# 03b_StepperMotorDriver.net
KiCad netlist of a schematic drawn in Altium Designer
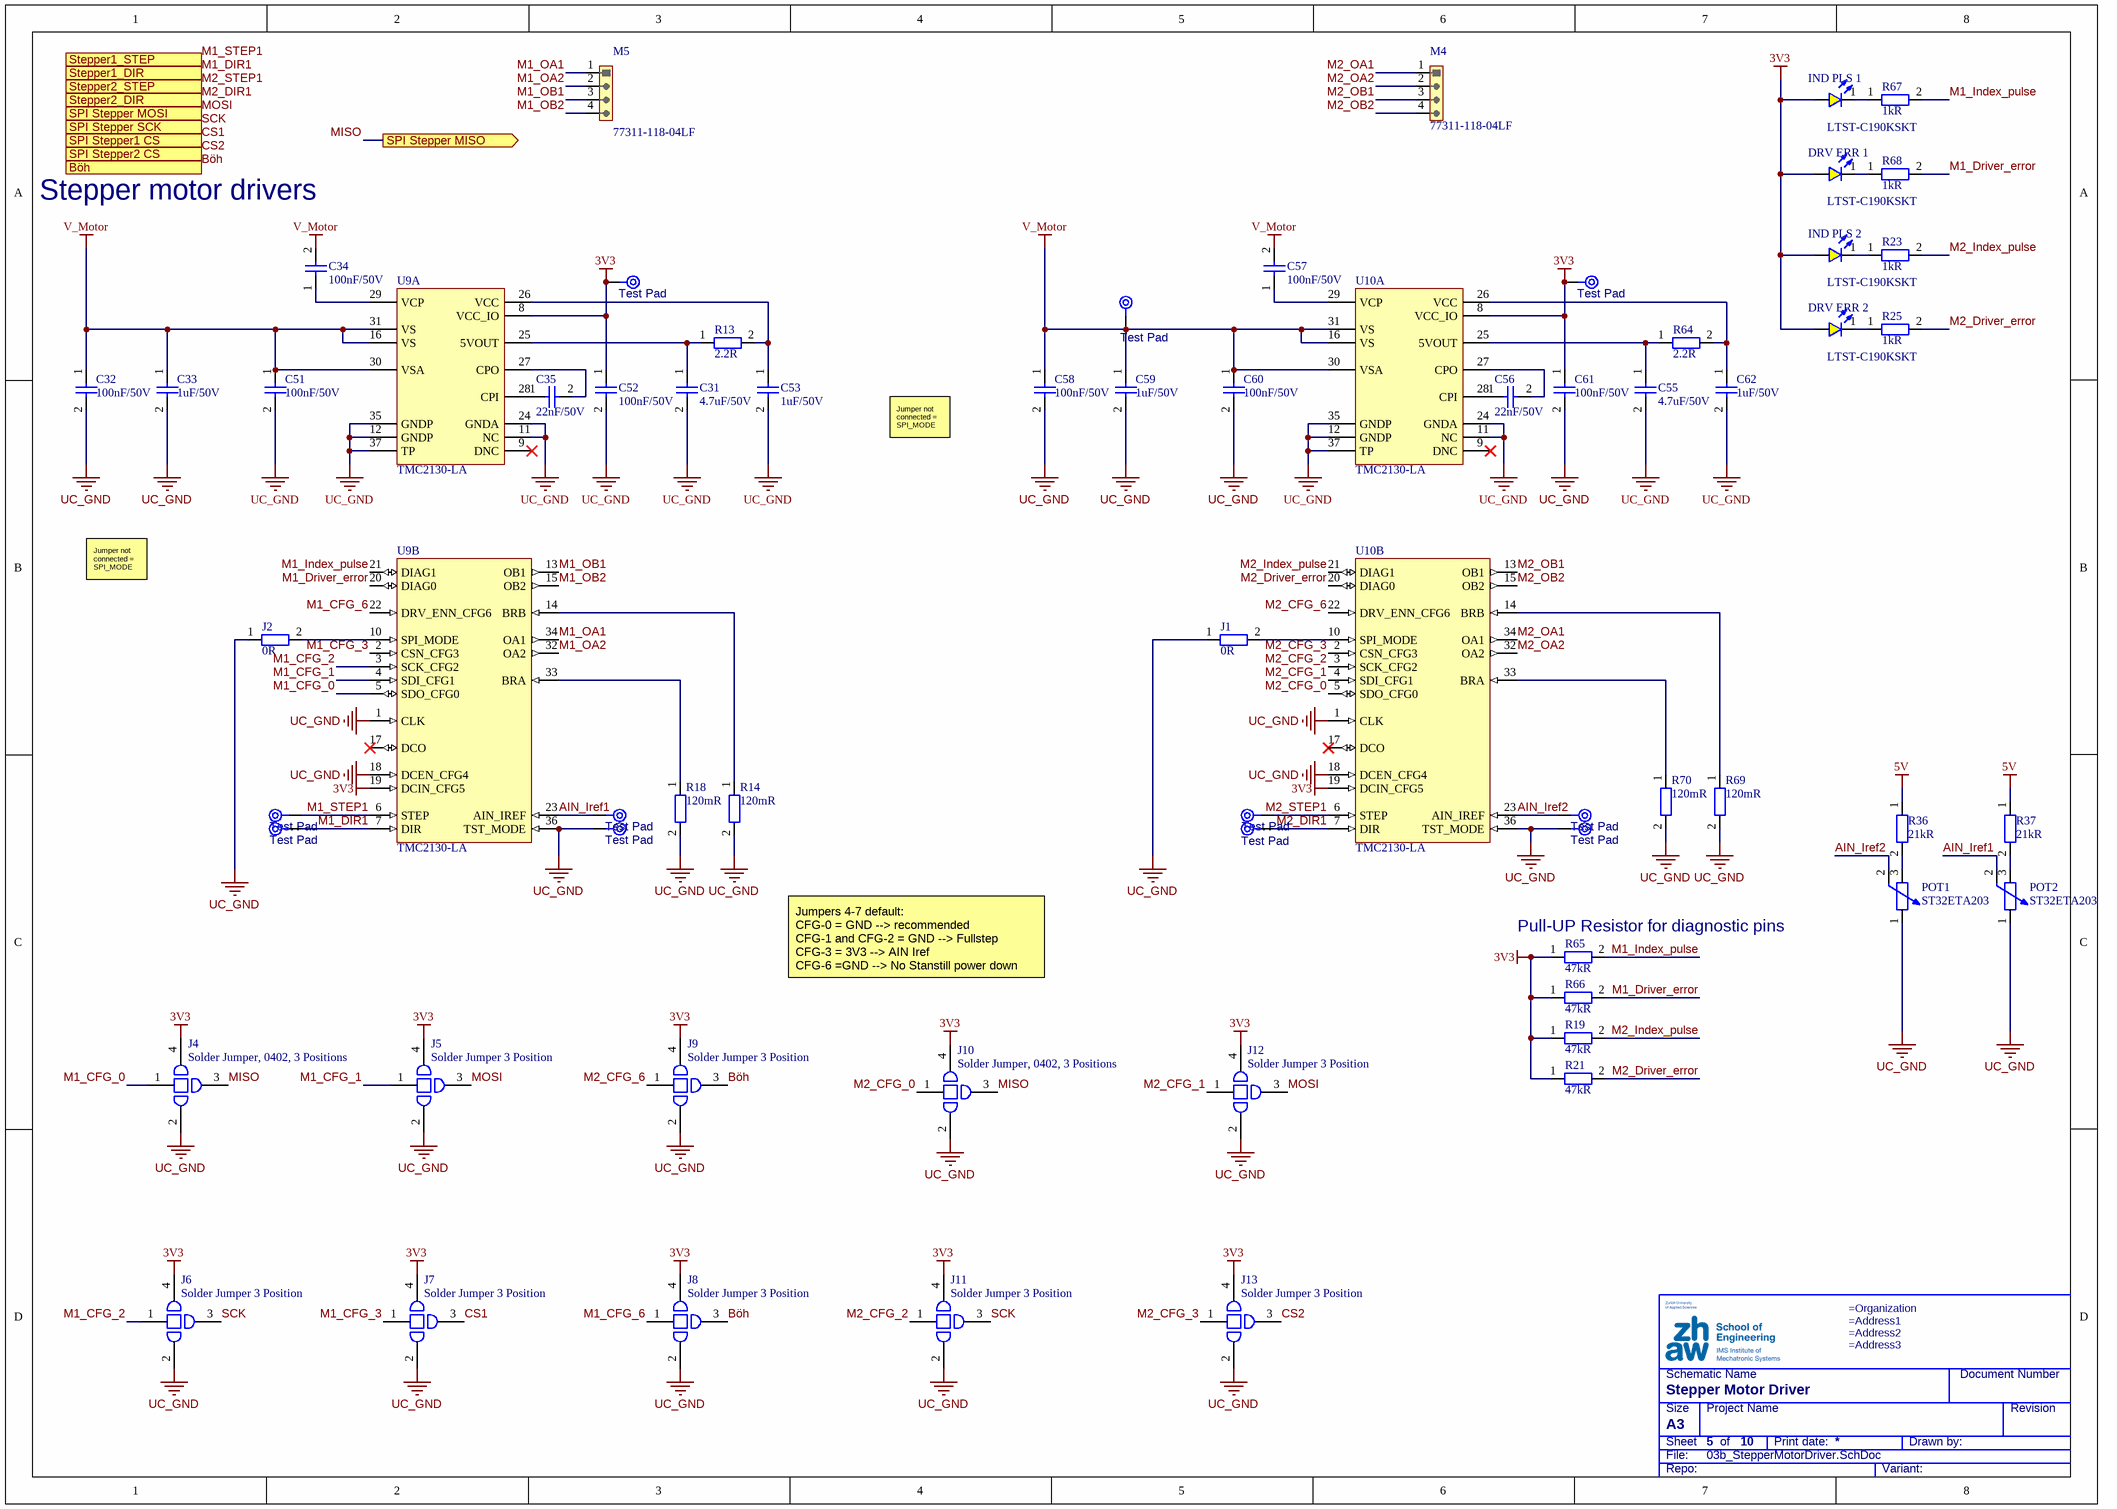
[diagram p0: 03b_StepperMotorDriver.SchDoc]

(export (version "E")
  (design (tool "Eeschema 10.0.6"))
  (components
    (comp (ref "6_M1_STEP")
      (value "Test Pad")
      (footprint "TP10R")
      (description "Test Pad 1.0 mm, SMD, d1.0")
      (libsource (lib "Altium Concord Pro on Altium 365") (part "Test Pad"))
    )
    (comp (ref "6_STEP_2")
      (value "Test Pad")
      (footprint "TP10R")
      (description "Test Pad 1.0 mm, SMD, d1.0")
      (libsource (lib "Altium Concord Pro on Altium 365") (part "Test Pad"))
    )
    (comp (ref "7_DIR_2")
      (value "Test Pad")
      (footprint "TP10R")
      (description "Test Pad 1.0 mm, SMD, d1.0")
      (libsource (lib "Altium Concord Pro on Altium 365") (part "Test Pad"))
    )
    (comp (ref "7_M1_DIR")
      (value "Test Pad")
      (footprint "TP10R")
      (description "Test Pad 1.0 mm, SMD, d1.0")
      (libsource (lib "Altium Concord Pro on Altium 365") (part "Test Pad"))
    )
    (comp (ref "8_VCC_IO")
      (value "Test Pad")
      (footprint "TP10R")
      (description "Test Pad 1.0 mm, SMD, d1.0")
      (libsource (lib "Altium Concord Pro on Altium 365") (part "Test Pad"))
    )
    (comp (ref "8_VCC_IO_2")
      (value "Test Pad")
      (footprint "TP10R")
      (description "Test Pad 1.0 mm, SMD, d1.0")
      (libsource (lib "Altium Concord Pro on Altium 365") (part "Test Pad"))
    )
    (comp (ref "16_31_VS_2")
      (value "Test Pad")
      (footprint "TP10R")
      (description "Test Pad 1.0 mm, SMD, d1.0")
      (libsource (lib "Altium Concord Pro on Altium 365") (part "Test Pad"))
    )
    (comp (ref "23_AIN_IREF")
      (value "Test Pad")
      (footprint "TP10R")
      (description "Test Pad 1.0 mm, SMD, d1.0")
      (libsource (lib "Altium Concord Pro on Altium 365") (part "Test Pad"))
    )
    (comp (ref "23_AIN_IREF_2")
      (value "Test Pad")
      (footprint "TP10R")
      (description "Test Pad 1.0 mm, SMD, d1.0")
      (libsource (lib "Altium Concord Pro on Altium 365") (part "Test Pad"))
    )
    (comp (ref "36_TST_MODE")
      (value "Test Pad")
      (footprint "TP10R")
      (description "Test Pad 1.0 mm, SMD, d1.0")
      (libsource (lib "Altium Concord Pro on Altium 365") (part "Test Pad"))
    )
    (comp (ref "36_TST_MODE_2")
      (value "Test Pad")
      (footprint "TP10R")
      (description "Test Pad 1.0 mm, SMD, d1.0")
      (libsource (lib "Altium Concord Pro on Altium 365") (part "Test Pad"))
    )
    (comp (ref "C31")
      (value "4.7uF/50V")
      (footprint "CAPC2012X15L")
      (description "Cap MLCC, 4.7uF, 50V, X5R, 10%, 0805")
      (fields (field (name "TOLERANCE") "10%"))
      (libsource (lib "Altium Concord Pro on Altium 365") (part "CAP-NP-2"))
    )
    (comp (ref "C32")
      (value "100nF/50V")
      (footprint "CAPC1005X05L")
      (description "Cap MLCC, 100nF, 50V, X7R, 10%, 0402")
      (fields (field (name "TOLERANCE") "10%"))
      (libsource (lib "Altium Concord Pro on Altium 365") (part "CAP-NP-2"))
    )
    (comp (ref "C33")
      (value "1uF/50V")
      (footprint "CAPC1608X09L")
      (description "Cap MLCC, 1uF, 50V, X5R, 10%, 0603")
      (fields (field (name "TOLERANCE") "10%"))
      (libsource (lib "Altium Concord Pro on Altium 365") (part "CAP-NP-2"))
    )
    (comp (ref "C34")
      (value "100nF/50V")
      (footprint "CAPC1005X05L")
      (description "Cap MLCC, 100nF, 50V, X7R, 10%, 0402")
      (fields (field (name "TOLERANCE") "10%"))
      (libsource (lib "Altium Concord Pro on Altium 365") (part "CAP-NP-2"))
    )
    (comp (ref "C35")
      (value "22nF/50V")
      (footprint "CAPC1005X05L")
      (description "Cap MLCC, 22nF, 50V, X7R, 10%, 0402")
      (fields (field (name "TOLERANCE") "10%"))
      (libsource (lib "Altium Concord Pro on Altium 365") (part "CAP-NP-2"))
    )
    (comp (ref "C51")
      (value "100nF/50V")
      (footprint "CAPC1005X05L")
      (description "Cap MLCC, 100nF, 50V, X7R, 10%, 0402")
      (fields (field (name "TOLERANCE") "10%"))
      (libsource (lib "Altium Concord Pro on Altium 365") (part "CAP-NP-2"))
    )
    (comp (ref "C52")
      (value "100nF/50V")
      (footprint "CAPC1005X05L")
      (description "Cap MLCC, 100nF, 50V, X7R, 10%, 0402")
      (fields (field (name "TOLERANCE") "10%"))
      (libsource (lib "Altium Concord Pro on Altium 365") (part "CAP-NP-2"))
    )
    (comp (ref "C53")
      (value "1uF/50V")
      (footprint "CAPC1608X09L")
      (description "Cap MLCC, 1uF, 50V, X5R, 10%, 0603")
      (fields (field (name "TOLERANCE") "10%"))
      (libsource (lib "Altium Concord Pro on Altium 365") (part "CAP-NP-2"))
    )
    (comp (ref "C55")
      (value "4.7uF/50V")
      (footprint "CAPC2012X15L")
      (description "Cap MLCC, 4.7uF, 50V, X5R, 10%, 0805")
      (fields (field (name "TOLERANCE") "10%"))
      (libsource (lib "Altium Concord Pro on Altium 365") (part "CAP-NP-2"))
    )
    (comp (ref "C56")
      (value "22nF/50V")
      (footprint "CAPC1005X05L")
      (description "Cap MLCC, 22nF, 50V, X7R, 10%, 0402")
      (fields (field (name "TOLERANCE") "10%"))
      (libsource (lib "Altium Concord Pro on Altium 365") (part "CAP-NP-2"))
    )
    (comp (ref "C57")
      (value "100nF/50V")
      (footprint "CAPC1005X05L")
      (description "Cap MLCC, 100nF, 50V, X7R, 10%, 0402")
      (fields (field (name "TOLERANCE") "10%"))
      (libsource (lib "Altium Concord Pro on Altium 365") (part "CAP-NP-2"))
    )
    (comp (ref "C58")
      (value "100nF/50V")
      (footprint "CAPC1005X05L")
      (description "Cap MLCC, 100nF, 50V, X7R, 10%, 0402")
      (fields (field (name "TOLERANCE") "10%"))
      (libsource (lib "Altium Concord Pro on Altium 365") (part "CAP-NP-2"))
    )
    (comp (ref "C59")
      (value "1uF/50V")
      (footprint "CAPC1608X09L")
      (description "Cap MLCC, 1uF, 50V, X5R, 10%, 0603")
      (fields (field (name "TOLERANCE") "10%"))
      (libsource (lib "Altium Concord Pro on Altium 365") (part "CAP-NP-2"))
    )
    (comp (ref "C60")
      (value "100nF/50V")
      (footprint "CAPC1005X05L")
      (description "Cap MLCC, 100nF, 50V, X7R, 10%, 0402")
      (fields (field (name "TOLERANCE") "10%"))
      (libsource (lib "Altium Concord Pro on Altium 365") (part "CAP-NP-2"))
    )
    (comp (ref "C61")
      (value "100nF/50V")
      (footprint "CAPC1005X05L")
      (description "Cap MLCC, 100nF, 50V, X7R, 10%, 0402")
      (fields (field (name "TOLERANCE") "10%"))
      (libsource (lib "Altium Concord Pro on Altium 365") (part "CAP-NP-2"))
    )
    (comp (ref "C62")
      (value "1uF/50V")
      (footprint "CAPC1608X09L")
      (description "Cap MLCC, 1uF, 50V, X5R, 10%, 0603")
      (fields (field (name "TOLERANCE") "10%"))
      (libsource (lib "Altium Concord Pro on Altium 365") (part "CAP-NP-2"))
    )
    (comp (ref "DRV ERR 1")
      (value "LTST-C190KSKT")
      (footprint "LEDSC160X80X80-2Lye")
      (description "LED, Yellow, 20mA, 2.0V, 0603")
      (libsource (lib "Altium Concord Pro on Altium 365") (part "LED-YELLOW-AK-2"))
    )
    (comp (ref "DRV ERR 2")
      (value "LTST-C190KSKT")
      (footprint "LEDSC160X80X80-2Lye")
      (description "LED, Yellow, 20mA, 2.0V, 0603")
      (libsource (lib "Altium Concord Pro on Altium 365") (part "LED-YELLOW-AK-2"))
    )
    (comp (ref "IND PLS 1")
      (value "LTST-C190KSKT")
      (footprint "LEDSC160X80X80-2Lye")
      (description "LED, Yellow, 20mA, 2.0V, 0603")
      (libsource (lib "Altium Concord Pro on Altium 365") (part "LED-YELLOW-AK-2"))
    )
    (comp (ref "IND PLS 2")
      (value "LTST-C190KSKT")
      (footprint "LEDSC160X80X80-2Lye")
      (description "LED, Yellow, 20mA, 2.0V, 0603")
      (libsource (lib "Altium Concord Pro on Altium 365") (part "LED-YELLOW-AK-2"))
    )
    (comp (ref "J1")
      (value "0R")
      (footprint "RESC1005X04L")
      (description "Res, 0R, 1%, 0.063W, 0402")
      (fields (field (name "POWER") "63mW") (field (name "TOLERANCE") "1%"))
      (libsource (lib "") (part "RES-2_1"))
    )
    (comp (ref "J2")
      (value "0R")
      (footprint "RESC1005X04L")
      (description "Res, 0R, 1%, 0.063W, 0402")
      (fields (field (name "POWER") "63mW") (field (name "TOLERANCE") "1%"))
      (libsource (lib "") (part "RES-2_1"))
    )
    (comp (ref "J4")
      (value "Solder Jumper, 0402, 3 Positions")
      (footprint "Solder Jumper 3 Positions, Position 1")
      (description "Solder Jumper, 0402, 3 Positions, SMD")
      (libsource (lib "Altium Concord Pro on Altium 365") (part "Solder Jumper 3 Position"))
    )
    (comp (ref "J5")
      (value "Solder Jumper 3 Position")
      (footprint "Solder Jumper, 0402, 3 Positions, DNP")
      (description "Solder Jumper, 0402, 3 Positions, SMD")
      (libsource (lib "Altium Concord Pro on Altium 365") (part "Solder Jumper 3 Position"))
    )
    (comp (ref "J6")
      (value "Solder Jumper 3 Position")
      (footprint "Solder Jumper, 0402, 3 Positions, DNP")
      (description "Solder Jumper, 0402, 3 Positions, SMD")
      (libsource (lib "Altium Concord Pro on Altium 365") (part "Solder Jumper 3 Position"))
    )
    (comp (ref "J7")
      (value "Solder Jumper 3 Position")
      (footprint "Solder Jumper, 0402, 3 Positions, DNP")
      (description "Solder Jumper, 0402, 3 Positions, SMD")
      (libsource (lib "Altium Concord Pro on Altium 365") (part "Solder Jumper 3 Position"))
    )
    (comp (ref "J8")
      (value "Solder Jumper 3 Position")
      (footprint "Solder Jumper 3 Positions, Position 2")
      (description "Solder Jumper, 0402, 3 Positions, SMD")
      (libsource (lib "Altium Concord Pro on Altium 365") (part "Solder Jumper 3 Position"))
    )
    (comp (ref "J9")
      (value "Solder Jumper 3 Position")
      (footprint "Solder Jumper 3 Positions, Position 2")
      (description "Solder Jumper, 0402, 3 Positions, SMD")
      (libsource (lib "Altium Concord Pro on Altium 365") (part "Solder Jumper 3 Position"))
    )
    (comp (ref "J10")
      (value "Solder Jumper, 0402, 3 Positions")
      (footprint "Solder Jumper 3 Positions, Position 1")
      (description "Solder Jumper, 0402, 3 Positions, SMD")
      (libsource (lib "Altium Concord Pro on Altium 365") (part "Solder Jumper 3 Position"))
    )
    (comp (ref "J11")
      (value "Solder Jumper 3 Position")
      (footprint "Solder Jumper, 0402, 3 Positions, DNP")
      (description "Solder Jumper, 0402, 3 Positions, SMD")
      (libsource (lib "Altium Concord Pro on Altium 365") (part "Solder Jumper 3 Position"))
    )
    (comp (ref "J12")
      (value "Solder Jumper 3 Position")
      (footprint "Solder Jumper, 0402, 3 Positions, DNP")
      (description "Solder Jumper, 0402, 3 Positions, SMD")
      (libsource (lib "Altium Concord Pro on Altium 365") (part "Solder Jumper 3 Position"))
    )
    (comp (ref "J13")
      (value "Solder Jumper 3 Position")
      (footprint "Solder Jumper, 0402, 3 Positions, DNP")
      (description "Solder Jumper, 0402, 3 Positions, SMD")
      (libsource (lib "Altium Concord Pro on Altium 365") (part "Solder Jumper 3 Position"))
    )
    (comp (ref "M4")
      (value "77311-118-04LF")
      (footprint "HD254_1X4_MV")
      (description "Header, 1x4Pin, Pitch 2.54mm, Male, Vertical, THT")
      (fields (field (name "MANUFACTURER") "FCI"))
      (libsource (lib "Altium Concord Pro on Altium 365") (part "Header 1x04 m"))
    )
    (comp (ref "M5")
      (value "77311-118-04LF")
      (footprint "HD254_1X4_MV")
      (description "Header, 1x4Pin, Pitch 2.54mm, Male, Vertical, THT")
      (fields (field (name "MANUFACTURER") "FCI"))
      (libsource (lib "Altium Concord Pro on Altium 365") (part "Header 1x04 m"))
    )
    (comp (ref "POT1")
      (value "ST32ETA203")
      (footprint "ST-32-Trimm")
      (description "Trim, 20kR, 10%, 0.125W, SMD")
      (fields (field (name "POWER") "125mW") (field (name "TOLERANCE") "20%"))
      (libsource (lib "Altium Concord Pro on Altium 365") (part "RES-POT-3"))
    )
    (comp (ref "POT2")
      (value "ST32ETA203")
      (footprint "ST-32-Trimm")
      (description "Trim, 20kR, 10%, 0.125W, SMD")
      (fields (field (name "POWER") "125mW") (field (name "TOLERANCE") "20%"))
      (libsource (lib "Altium Concord Pro on Altium 365") (part "RES-POT-3"))
    )
    (comp (ref "R13")
      (value "2.2R")
      (footprint "RESC1005X04L")
      (description "Res, 2.2R, 1%, 0.063W, 0402")
      (fields (field (name "POWER") "63mW") (field (name "TOLERANCE") "1%"))
      (libsource (lib "") (part "RES-2_2"))
    )
    (comp (ref "R14")
      (value "120mR")
      (footprint "RESC1632X06")
      (description "Res, 120mR, 1%, 1W, 0612")
      (fields (field (name "POWER") "1W") (field (name "TOLERANCE") "1%"))
      (libsource (lib "Altium Concord Pro on Altium 365") (part "RES-2"))
    )
    (comp (ref "R18")
      (value "120mR")
      (footprint "RESC1632X06")
      (description "Res, 120mR, 1%, 1W, 0612")
      (fields (field (name "POWER") "1W") (field (name "TOLERANCE") "1%"))
      (libsource (lib "Altium Concord Pro on Altium 365") (part "RES-2"))
    )
    (comp (ref "R19")
      (value "47kR")
      (footprint "RESC1005X04L")
      (description "Res, 47kR, 1%, 0.063W, 0402")
      (fields (field (name "POWER") "63mW") (field (name "TOLERANCE") "1%"))
      (libsource (lib "") (part "RES-2_1"))
    )
    (comp (ref "R21")
      (value "47kR")
      (footprint "RESC1005X04L")
      (description "Res, 47kR, 1%, 0.063W, 0402")
      (fields (field (name "POWER") "63mW") (field (name "TOLERANCE") "1%"))
      (libsource (lib "") (part "RES-2_1"))
    )
    (comp (ref "R23")
      (value "1kR")
      (footprint "RESC1005X04L")
      (description "Res, 1kR, 1%, 0.1W, 0402")
      (fields (field (name "POWER") "100mW") (field (name "TOLERANCE") "1%"))
      (libsource (lib "") (part "RES-2_1"))
    )
    (comp (ref "R25")
      (value "1kR")
      (footprint "RESC1005X04L")
      (description "Res, 1kR, 1%, 0.1W, 0402")
      (fields (field (name "POWER") "100mW") (field (name "TOLERANCE") "1%"))
      (libsource (lib "") (part "RES-2_1"))
    )
    (comp (ref "R36")
      (value "21kR")
      (footprint "RESC1005X04L")
      (description "Res, 21kR, 1%, 0.063W, 0402")
      (fields (field (name "POWER") "63mW") (field (name "TOLERANCE") "1%"))
      (libsource (lib "Altium Concord Pro on Altium 365") (part "RES-2"))
    )
    (comp (ref "R37")
      (value "21kR")
      (footprint "RESC1005X04L")
      (description "Res, 21kR, 1%, 0.063W, 0402")
      (fields (field (name "POWER") "63mW") (field (name "TOLERANCE") "1%"))
      (libsource (lib "Altium Concord Pro on Altium 365") (part "RES-2"))
    )
    (comp (ref "R64")
      (value "2.2R")
      (footprint "RESC1005X04L")
      (description "Res, 2.2R, 1%, 0.063W, 0402")
      (fields (field (name "POWER") "63mW") (field (name "TOLERANCE") "1%"))
      (libsource (lib "") (part "RES-2_1"))
    )
    (comp (ref "R65")
      (value "47kR")
      (footprint "RESC1005X04L")
      (description "Res, 47kR, 1%, 0.063W, 0402")
      (fields (field (name "POWER") "63mW") (field (name "TOLERANCE") "1%"))
      (libsource (lib "") (part "RES-2_1"))
    )
    (comp (ref "R66")
      (value "47kR")
      (footprint "RESC1005X04L")
      (description "Res, 47kR, 1%, 0.063W, 0402")
      (fields (field (name "POWER") "63mW") (field (name "TOLERANCE") "1%"))
      (libsource (lib "") (part "RES-2_1"))
    )
    (comp (ref "R67")
      (value "1kR")
      (footprint "RESC1005X04L")
      (description "Res, 1kR, 1%, 0.1W, 0402")
      (fields (field (name "POWER") "100mW") (field (name "TOLERANCE") "1%"))
      (libsource (lib "") (part "RES-2_1"))
    )
    (comp (ref "R68")
      (value "1kR")
      (footprint "RESC1005X04L")
      (description "Res, 1kR, 1%, 0.1W, 0402")
      (fields (field (name "POWER") "100mW") (field (name "TOLERANCE") "1%"))
      (libsource (lib "") (part "RES-2_1"))
    )
    (comp (ref "R69")
      (value "120mR")
      (footprint "RESC1632X06")
      (description "Res, 120mR, 1%, 1W, 0612")
      (fields (field (name "POWER") "1W") (field (name "TOLERANCE") "1%"))
      (libsource (lib "Altium Concord Pro on Altium 365") (part "RES-2"))
    )
    (comp (ref "R70")
      (value "120mR")
      (footprint "RESC1632X06")
      (description "Res, 120mR, 1%, 1W, 0612")
      (fields (field (name "POWER") "1W") (field (name "TOLERANCE") "1%"))
      (libsource (lib "Altium Concord Pro on Altium 365") (part "RES-2"))
    )
    (comp (ref "U9")
      (value "TMC2130-LA")
      (footprint "QFN50P500X600X80-37T360X410L")
      (description "Stepper Motor Driver, 1Ch, 3..5.5V, Power 4.75..46V, 2A, QFN-36")
      (libsource (lib "Altium Concord Pro on Altium 365") (part "TMC2130"))
    )
    (comp (ref "U10")
      (value "TMC2130-LA")
      (footprint "QFN50P500X600X80-37T360X410L")
      (description "Stepper Motor Driver, 1Ch, 3..5.5V, Power 4.75..46V, 2A, QFN-36")
      (libsource (lib "Altium Concord Pro on Altium 365") (part "TMC2130"))
    )
  )
  (nets
    (net (code "1") (name "/AIN_Iref1") (class "Default")
      (node (ref "23_AIN_IREF") (pin "1") (pinfunction "TP_1") (pintype "passive"))
      (node (ref "POT2") (pin "2") (pinfunction "S_2") (pintype "passive"))
      (node (ref "U9") (pin "23") (pinfunction "AIN_IREF_23") (pintype "input"))
    )
    (net (code "2") (name "/AIN_Iref2") (class "Default")
      (node (ref "23_AIN_IREF_2") (pin "1") (pinfunction "TP_1") (pintype "passive"))
      (node (ref "POT1") (pin "2") (pinfunction "S_2") (pintype "passive"))
      (node (ref "U10") (pin "23") (pinfunction "AIN_IREF_23") (pintype "input"))
    )
    (net (code "3") (name "/Böh") (class "Default")
      (node (ref "J8") (pin "3") (pinfunction "3_3") (pintype "passive"))
      (node (ref "J9") (pin "3") (pinfunction "3_3") (pintype "passive"))
    )
    (net (code "4") (name "/CS1") (class "Default")
      (node (ref "J7") (pin "3") (pinfunction "3_3") (pintype "passive"))
    )
    (net (code "5") (name "/CS2") (class "Default")
      (node (ref "J13") (pin "3") (pinfunction "3_3") (pintype "passive"))
    )
    (net (code "6") (name "/M1_CFG_0") (class "Default")
      (node (ref "J4") (pin "1") (pinfunction "1_1") (pintype "passive"))
      (node (ref "U9") (pin "5") (pinfunction "SDO_CFG0_5") (pintype "bidirectional"))
    )
    (net (code "7") (name "/M1_CFG_1") (class "Default")
      (node (ref "J5") (pin "1") (pinfunction "1_1") (pintype "passive"))
      (node (ref "U9") (pin "4") (pinfunction "SDI_CFG1_4") (pintype "input"))
    )
    (net (code "8") (name "/M1_CFG_2") (class "Default")
      (node (ref "J6") (pin "1") (pinfunction "1_1") (pintype "passive"))
      (node (ref "U9") (pin "3") (pinfunction "SCK_CFG2_3") (pintype "input"))
    )
    (net (code "9") (name "/M1_CFG_3") (class "Default")
      (node (ref "J7") (pin "1") (pinfunction "1_1") (pintype "passive"))
      (node (ref "U9") (pin "2") (pinfunction "CSN_CFG3_2") (pintype "input"))
    )
    (net (code "10") (name "/M1_CFG_6") (class "Default")
      (node (ref "J8") (pin "1") (pinfunction "1_1") (pintype "passive"))
      (node (ref "U9") (pin "22") (pinfunction "DRV_ENN_CFG6_22") (pintype "input"))
    )
    (net (code "11") (name "/M1_DIR1") (class "Default")
      (node (ref "7_M1_DIR") (pin "1") (pinfunction "TP_1") (pintype "passive"))
      (node (ref "U9") (pin "7") (pinfunction "DIR_7") (pintype "input"))
    )
    (net (code "12") (name "/M1_Driver_error") (class "Default")
      (node (ref "R66") (pin "2") (pinfunction "2_2") (pintype "passive"))
      (node (ref "R68") (pin "2") (pinfunction "2_2") (pintype "passive"))
      (node (ref "U9") (pin "20") (pinfunction "DIAG0_20") (pintype "bidirectional"))
    )
    (net (code "13") (name "/M1_Index_pulse") (class "Default")
      (node (ref "R65") (pin "2") (pinfunction "2_2") (pintype "passive"))
      (node (ref "R67") (pin "2") (pinfunction "2_2") (pintype "passive"))
      (node (ref "U9") (pin "21") (pinfunction "DIAG1_21") (pintype "bidirectional"))
    )
    (net (code "14") (name "/M1_OA1") (class "Default")
      (node (ref "M5") (pin "1") (pinfunction "1_1") (pintype "passive"))
      (node (ref "U9") (pin "34") (pinfunction "OA1_34") (pintype "output"))
    )
    (net (code "15") (name "/M1_OA2") (class "Default")
      (node (ref "M5") (pin "2") (pinfunction "2_2") (pintype "passive"))
      (node (ref "U9") (pin "32") (pinfunction "OA2_32") (pintype "output"))
    )
    (net (code "16") (name "/M1_OB1") (class "Default")
      (node (ref "M5") (pin "3") (pinfunction "3_3") (pintype "passive"))
      (node (ref "U9") (pin "13") (pinfunction "OB1_13") (pintype "output"))
    )
    (net (code "17") (name "/M1_OB2") (class "Default")
      (node (ref "M5") (pin "4") (pinfunction "4_4") (pintype "passive"))
      (node (ref "U9") (pin "15") (pinfunction "OB2_15") (pintype "output"))
    )
    (net (code "18") (name "/M1_STEP1") (class "Default")
      (node (ref "6_M1_STEP") (pin "1") (pinfunction "TP_1") (pintype "passive"))
      (node (ref "U9") (pin "6") (pinfunction "STEP_6") (pintype "input"))
    )
    (net (code "19") (name "/M2_CFG_0") (class "Default")
      (node (ref "J10") (pin "1") (pinfunction "1_1") (pintype "passive"))
      (node (ref "U10") (pin "5") (pinfunction "SDO_CFG0_5") (pintype "bidirectional"))
    )
    (net (code "20") (name "/M2_CFG_1") (class "Default")
      (node (ref "J12") (pin "1") (pinfunction "1_1") (pintype "passive"))
      (node (ref "U10") (pin "4") (pinfunction "SDI_CFG1_4") (pintype "input"))
    )
    (net (code "21") (name "/M2_CFG_2") (class "Default")
      (node (ref "J11") (pin "1") (pinfunction "1_1") (pintype "passive"))
      (node (ref "U10") (pin "3") (pinfunction "SCK_CFG2_3") (pintype "input"))
    )
    (net (code "22") (name "/M2_CFG_3") (class "Default")
      (node (ref "J13") (pin "1") (pinfunction "1_1") (pintype "passive"))
      (node (ref "U10") (pin "2") (pinfunction "CSN_CFG3_2") (pintype "input"))
    )
    (net (code "23") (name "/M2_CFG_6") (class "Default")
      (node (ref "J9") (pin "1") (pinfunction "1_1") (pintype "passive"))
      (node (ref "U10") (pin "22") (pinfunction "DRV_ENN_CFG6_22") (pintype "input"))
    )
    (net (code "24") (name "/M2_DIR1") (class "Default")
      (node (ref "7_DIR_2") (pin "1") (pinfunction "TP_1") (pintype "passive"))
      (node (ref "U10") (pin "7") (pinfunction "DIR_7") (pintype "input"))
    )
    (net (code "25") (name "/M2_Driver_error") (class "Default")
      (node (ref "R21") (pin "2") (pinfunction "2_2") (pintype "passive"))
      (node (ref "R25") (pin "2") (pinfunction "2_2") (pintype "passive"))
      (node (ref "U10") (pin "20") (pinfunction "DIAG0_20") (pintype "bidirectional"))
    )
    (net (code "26") (name "/M2_Index_pulse") (class "Default")
      (node (ref "R19") (pin "2") (pinfunction "2_2") (pintype "passive"))
      (node (ref "R23") (pin "2") (pinfunction "2_2") (pintype "passive"))
      (node (ref "U10") (pin "21") (pinfunction "DIAG1_21") (pintype "bidirectional"))
    )
    (net (code "27") (name "/M2_OA1") (class "Default")
      (node (ref "M4") (pin "1") (pinfunction "1_1") (pintype "passive"))
      (node (ref "U10") (pin "34") (pinfunction "OA1_34") (pintype "output"))
    )
    (net (code "28") (name "/M2_OA2") (class "Default")
      (node (ref "M4") (pin "2") (pinfunction "2_2") (pintype "passive"))
      (node (ref "U10") (pin "32") (pinfunction "OA2_32") (pintype "output"))
    )
    (net (code "29") (name "/M2_OB1") (class "Default")
      (node (ref "M4") (pin "3") (pinfunction "3_3") (pintype "passive"))
      (node (ref "U10") (pin "13") (pinfunction "OB1_13") (pintype "output"))
    )
    (net (code "30") (name "/M2_OB2") (class "Default")
      (node (ref "M4") (pin "4") (pinfunction "4_4") (pintype "passive"))
      (node (ref "U10") (pin "15") (pinfunction "OB2_15") (pintype "output"))
    )
    (net (code "31") (name "/M2_STEP1") (class "Default")
      (node (ref "6_STEP_2") (pin "1") (pinfunction "TP_1") (pintype "passive"))
      (node (ref "U10") (pin "6") (pinfunction "STEP_6") (pintype "input"))
    )
    (net (code "32") (name "/MISO") (class "Default")
      (node (ref "J10") (pin "3") (pinfunction "3_3") (pintype "passive"))
      (node (ref "J4") (pin "3") (pinfunction "3_3") (pintype "passive"))
    )
    (net (code "33") (name "/MOSI") (class "Default")
      (node (ref "J12") (pin "3") (pinfunction "3_3") (pintype "passive"))
      (node (ref "J5") (pin "3") (pinfunction "3_3") (pintype "passive"))
    )
    (net (code "34") (name "/SCK") (class "Default")
      (node (ref "J11") (pin "3") (pinfunction "3_3") (pintype "passive"))
      (node (ref "J6") (pin "3") (pinfunction "3_3") (pintype "passive"))
    )
    (net (code "35") (name "3V3") (class "Default")
      (node (ref "8_VCC_IO") (pin "1") (pinfunction "TP_1") (pintype "passive"))
      (node (ref "8_VCC_IO_2") (pin "1") (pinfunction "TP_1") (pintype "passive"))
      (node (ref "C52") (pin "1") (pinfunction "1_1") (pintype "passive"))
      (node (ref "C61") (pin "1") (pinfunction "1_1") (pintype "passive"))
      (node (ref "DRV ERR 1") (pin "2") (pinfunction "A_2") (pintype "passive"))
      (node (ref "DRV ERR 2") (pin "2") (pinfunction "A_2") (pintype "passive"))
      (node (ref "IND PLS 1") (pin "2") (pinfunction "A_2") (pintype "passive"))
      (node (ref "IND PLS 2") (pin "2") (pinfunction "A_2") (pintype "passive"))
      (node (ref "J10") (pin "4") (pinfunction "4_4") (pintype "passive"))
      (node (ref "J11") (pin "4") (pinfunction "4_4") (pintype "passive"))
      (node (ref "J12") (pin "4") (pinfunction "4_4") (pintype "passive"))
      (node (ref "J13") (pin "4") (pinfunction "4_4") (pintype "passive"))
      (node (ref "J4") (pin "4") (pinfunction "4_4") (pintype "passive"))
      (node (ref "J5") (pin "4") (pinfunction "4_4") (pintype "passive"))
      (node (ref "J6") (pin "4") (pinfunction "4_4") (pintype "passive"))
      (node (ref "J7") (pin "4") (pinfunction "4_4") (pintype "passive"))
      (node (ref "J8") (pin "4") (pinfunction "4_4") (pintype "passive"))
      (node (ref "J9") (pin "4") (pinfunction "4_4") (pintype "passive"))
      (node (ref "R19") (pin "1") (pinfunction "1_1") (pintype "passive"))
      (node (ref "R21") (pin "1") (pinfunction "1_1") (pintype "passive"))
      (node (ref "R65") (pin "1") (pinfunction "1_1") (pintype "passive"))
      (node (ref "R66") (pin "1") (pinfunction "1_1") (pintype "passive"))
      (node (ref "U10") (pin "19") (pinfunction "DCIN_CFG5_19") (pintype "input"))
      (node (ref "U10") (pin "8") (pinfunction "VCC_IO_8") (pintype "power_in"))
      (node (ref "U9") (pin "19") (pinfunction "DCIN_CFG5_19") (pintype "input"))
      (node (ref "U9") (pin "8") (pinfunction "VCC_IO_8") (pintype "power_in"))
    )
    (net (code "36") (name "5V") (class "Default")
      (node (ref "R36") (pin "1") (pinfunction "1_1") (pintype "passive"))
      (node (ref "R37") (pin "1") (pinfunction "1_1") (pintype "passive"))
    )
    (net (code "37") (name "Net-(DRV ERR 1-K)") (class "Default")
      (node (ref "DRV ERR 1") (pin "1") (pinfunction "K_1") (pintype "passive"))
      (node (ref "R68") (pin "1") (pinfunction "1_1") (pintype "passive"))
    )
    (net (code "38") (name "Net-(DRV ERR 2-K)") (class "Default")
      (node (ref "DRV ERR 2") (pin "1") (pinfunction "K_1") (pintype "passive"))
      (node (ref "R25") (pin "1") (pinfunction "1_1") (pintype "passive"))
    )
    (net (code "39") (name "Net-(IND PLS 1-K)") (class "Default")
      (node (ref "IND PLS 1") (pin "1") (pinfunction "K_1") (pintype "passive"))
      (node (ref "R67") (pin "1") (pinfunction "1_1") (pintype "passive"))
    )
    (net (code "40") (name "Net-(IND PLS 2-K)") (class "Default")
      (node (ref "IND PLS 2") (pin "1") (pinfunction "K_1") (pintype "passive"))
      (node (ref "R23") (pin "1") (pinfunction "1_1") (pintype "passive"))
    )
    (net (code "41") (name "Net-(POT1-CW)") (class "Default")
      (node (ref "POT1") (pin "3") (pinfunction "CW_3") (pintype "passive"))
      (node (ref "R36") (pin "2") (pinfunction "2_2") (pintype "passive"))
    )
    (net (code "42") (name "Net-(POT2-CW)") (class "Default")
      (node (ref "POT2") (pin "3") (pinfunction "CW_3") (pintype "passive"))
      (node (ref "R37") (pin "2") (pinfunction "2_2") (pintype "passive"))
    )
    (net (code "43") (name "Net-(U9A-5VOUT)") (class "Default")
      (node (ref "C31") (pin "1") (pinfunction "1_1") (pintype "passive"))
      (node (ref "R13") (pin "1") (pinfunction "1_1") (pintype "passive"))
      (node (ref "U9") (pin "25") (pinfunction "5VOUT_25") (pintype "power_in"))
    )
    (net (code "44") (name "Net-(U9A-CPI)") (class "Default")
      (node (ref "C35") (pin "1") (pinfunction "1_1") (pintype "passive"))
      (node (ref "U9") (pin "28") (pinfunction "CPI_28") (pintype "power_in"))
    )
    (net (code "45") (name "Net-(U9A-CPO)") (class "Default")
      (node (ref "C35") (pin "2") (pinfunction "2_2") (pintype "passive"))
      (node (ref "U9") (pin "27") (pinfunction "CPO_27") (pintype "power_in"))
    )
    (net (code "46") (name "Net-(U9A-VCC)") (class "Default")
      (node (ref "C53") (pin "1") (pinfunction "1_1") (pintype "passive"))
      (node (ref "R13") (pin "2") (pinfunction "2_2") (pintype "passive"))
      (node (ref "U9") (pin "26") (pinfunction "VCC_26") (pintype "power_in"))
    )
    (net (code "47") (name "Net-(U9A-VCP)") (class "Default")
      (node (ref "C34") (pin "1") (pinfunction "1_1") (pintype "passive"))
      (node (ref "U9") (pin "29") (pinfunction "VCP_29") (pintype "power_in"))
    )
    (net (code "48") (name "Net-(U9B-BRA)") (class "Default")
      (node (ref "R18") (pin "1") (pinfunction "1_1") (pintype "passive"))
      (node (ref "U9") (pin "33") (pinfunction "BRA_33") (pintype "input"))
    )
    (net (code "49") (name "Net-(U9B-BRB)") (class "Default")
      (node (ref "R14") (pin "1") (pinfunction "1_1") (pintype "passive"))
      (node (ref "U9") (pin "14") (pinfunction "BRB_14") (pintype "input"))
    )
    (net (code "50") (name "Net-(U9B-SPI_MODE)") (class "Default")
      (node (ref "J2") (pin "2") (pinfunction "2_2") (pintype "passive"))
      (node (ref "U9") (pin "10") (pinfunction "SPI_MODE_10") (pintype "input"))
    )
    (net (code "51") (name "Net-(U10A-5VOUT)") (class "Default")
      (node (ref "C55") (pin "1") (pinfunction "1_1") (pintype "passive"))
      (node (ref "R64") (pin "1") (pinfunction "1_1") (pintype "passive"))
      (node (ref "U10") (pin "25") (pinfunction "5VOUT_25") (pintype "power_in"))
    )
    (net (code "52") (name "Net-(U10A-CPI)") (class "Default")
      (node (ref "C56") (pin "1") (pinfunction "1_1") (pintype "passive"))
      (node (ref "U10") (pin "28") (pinfunction "CPI_28") (pintype "power_in"))
    )
    (net (code "53") (name "Net-(U10A-CPO)") (class "Default")
      (node (ref "C56") (pin "2") (pinfunction "2_2") (pintype "passive"))
      (node (ref "U10") (pin "27") (pinfunction "CPO_27") (pintype "power_in"))
    )
    (net (code "54") (name "Net-(U10A-VCC)") (class "Default")
      (node (ref "C62") (pin "1") (pinfunction "1_1") (pintype "passive"))
      (node (ref "R64") (pin "2") (pinfunction "2_2") (pintype "passive"))
      (node (ref "U10") (pin "26") (pinfunction "VCC_26") (pintype "power_in"))
    )
    (net (code "55") (name "Net-(U10A-VCP)") (class "Default")
      (node (ref "C57") (pin "1") (pinfunction "1_1") (pintype "passive"))
      (node (ref "U10") (pin "29") (pinfunction "VCP_29") (pintype "power_in"))
    )
    (net (code "56") (name "Net-(U10B-BRA)") (class "Default")
      (node (ref "R70") (pin "1") (pinfunction "1_1") (pintype "passive"))
      (node (ref "U10") (pin "33") (pinfunction "BRA_33") (pintype "input"))
    )
    (net (code "57") (name "Net-(U10B-BRB)") (class "Default")
      (node (ref "R69") (pin "1") (pinfunction "1_1") (pintype "passive"))
      (node (ref "U10") (pin "14") (pinfunction "BRB_14") (pintype "input"))
    )
    (net (code "58") (name "Net-(U10B-SPI_MODE)") (class "Default")
      (node (ref "J1") (pin "2") (pinfunction "2_2") (pintype "passive"))
      (node (ref "U10") (pin "10") (pinfunction "SPI_MODE_10") (pintype "input"))
    )
    (net (code "59") (name "UC_GND") (class "Default")
      (node (ref "36_TST_MODE") (pin "1") (pinfunction "TP_1") (pintype "passive"))
      (node (ref "36_TST_MODE_2") (pin "1") (pinfunction "TP_1") (pintype "passive"))
      (node (ref "C31") (pin "2") (pinfunction "2_2") (pintype "passive"))
      (node (ref "C32") (pin "2") (pinfunction "2_2") (pintype "passive"))
      (node (ref "C33") (pin "2") (pinfunction "2_2") (pintype "passive"))
      (node (ref "C51") (pin "2") (pinfunction "2_2") (pintype "passive"))
      (node (ref "C52") (pin "2") (pinfunction "2_2") (pintype "passive"))
      (node (ref "C53") (pin "2") (pinfunction "2_2") (pintype "passive"))
      (node (ref "C55") (pin "2") (pinfunction "2_2") (pintype "passive"))
      (node (ref "C58") (pin "2") (pinfunction "2_2") (pintype "passive"))
      (node (ref "C59") (pin "2") (pinfunction "2_2") (pintype "passive"))
      (node (ref "C60") (pin "2") (pinfunction "2_2") (pintype "passive"))
      (node (ref "C61") (pin "2") (pinfunction "2_2") (pintype "passive"))
      (node (ref "C62") (pin "2") (pinfunction "2_2") (pintype "passive"))
      (node (ref "J1") (pin "1") (pinfunction "1_1") (pintype "passive"))
      (node (ref "J10") (pin "2") (pinfunction "2_2") (pintype "passive"))
      (node (ref "J11") (pin "2") (pinfunction "2_2") (pintype "passive"))
      (node (ref "J12") (pin "2") (pinfunction "2_2") (pintype "passive"))
      (node (ref "J13") (pin "2") (pinfunction "2_2") (pintype "passive"))
      (node (ref "J2") (pin "1") (pinfunction "1_1") (pintype "passive"))
      (node (ref "J4") (pin "2") (pinfunction "2_2") (pintype "passive"))
      (node (ref "J5") (pin "2") (pinfunction "2_2") (pintype "passive"))
      (node (ref "J6") (pin "2") (pinfunction "2_2") (pintype "passive"))
      (node (ref "J7") (pin "2") (pinfunction "2_2") (pintype "passive"))
      (node (ref "J8") (pin "2") (pinfunction "2_2") (pintype "passive"))
      (node (ref "J9") (pin "2") (pinfunction "2_2") (pintype "passive"))
      (node (ref "POT1") (pin "1") (pinfunction "CCW_1") (pintype "passive"))
      (node (ref "POT2") (pin "1") (pinfunction "CCW_1") (pintype "passive"))
      (node (ref "R14") (pin "2") (pinfunction "2_2") (pintype "passive"))
      (node (ref "R18") (pin "2") (pinfunction "2_2") (pintype "passive"))
      (node (ref "R69") (pin "2") (pinfunction "2_2") (pintype "passive"))
      (node (ref "R70") (pin "2") (pinfunction "2_2") (pintype "passive"))
      (node (ref "U10") (pin "1") (pinfunction "CLK_1") (pintype "input"))
      (node (ref "U10") (pin "11") (pinfunction "NC_11") (pintype "passive"))
      (node (ref "U10") (pin "12") (pinfunction "GNDP_12") (pintype "power_in"))
      (node (ref "U10") (pin "18") (pinfunction "DCEN_CFG4_18") (pintype "input"))
      (node (ref "U10") (pin "24") (pinfunction "GNDA_24") (pintype "power_in"))
      (node (ref "U10") (pin "35") (pinfunction "GNDP_35") (pintype "power_in"))
      (node (ref "U10") (pin "36") (pinfunction "TST_MODE_36") (pintype "input"))
      (node (ref "U10") (pin "37") (pinfunction "TP_37") (pintype "power_in"))
      (node (ref "U9") (pin "1") (pinfunction "CLK_1") (pintype "input"))
      (node (ref "U9") (pin "11") (pinfunction "NC_11") (pintype "passive"))
      (node (ref "U9") (pin "12") (pinfunction "GNDP_12") (pintype "power_in"))
      (node (ref "U9") (pin "18") (pinfunction "DCEN_CFG4_18") (pintype "input"))
      (node (ref "U9") (pin "24") (pinfunction "GNDA_24") (pintype "power_in"))
      (node (ref "U9") (pin "35") (pinfunction "GNDP_35") (pintype "power_in"))
      (node (ref "U9") (pin "36") (pinfunction "TST_MODE_36") (pintype "input"))
      (node (ref "U9") (pin "37") (pinfunction "TP_37") (pintype "power_in"))
    )
    (net (code "60") (name "V_Motor") (class "Default")
      (node (ref "16_31_VS_2") (pin "1") (pinfunction "TP_1") (pintype "passive"))
      (node (ref "C32") (pin "1") (pinfunction "1_1") (pintype "passive"))
      (node (ref "C33") (pin "1") (pinfunction "1_1") (pintype "passive"))
      (node (ref "C34") (pin "2") (pinfunction "2_2") (pintype "passive"))
      (node (ref "C51") (pin "1") (pinfunction "1_1") (pintype "passive"))
      (node (ref "C57") (pin "2") (pinfunction "2_2") (pintype "passive"))
      (node (ref "C58") (pin "1") (pinfunction "1_1") (pintype "passive"))
      (node (ref "C59") (pin "1") (pinfunction "1_1") (pintype "passive"))
      (node (ref "C60") (pin "1") (pinfunction "1_1") (pintype "passive"))
      (node (ref "U10") (pin "16") (pinfunction "VS_16") (pintype "power_in"))
      (node (ref "U10") (pin "30") (pinfunction "VSA_30") (pintype "power_in"))
      (node (ref "U10") (pin "31") (pinfunction "VS_31") (pintype "power_in"))
      (node (ref "U9") (pin "16") (pinfunction "VS_16") (pintype "power_in"))
      (node (ref "U9") (pin "30") (pinfunction "VSA_30") (pintype "power_in"))
      (node (ref "U9") (pin "31") (pinfunction "VS_31") (pintype "power_in"))
    )
    (net (code "61") (name "unconnected-(U9A-DNC-Pad9)") (class "Default")
      (node (ref "U9") (pin "9") (pinfunction "DNC_9") (pintype "passive+no_connect"))
    )
    (net (code "62") (name "unconnected-(U9B-DCO-Pad17)") (class "Default")
      (node (ref "U9") (pin "17") (pinfunction "DCO_17") (pintype "bidirectional+no_connect"))
    )
    (net (code "63") (name "unconnected-(U10A-DNC-Pad9)") (class "Default")
      (node (ref "U10") (pin "9") (pinfunction "DNC_9") (pintype "passive+no_connect"))
    )
    (net (code "64") (name "unconnected-(U10B-DCO-Pad17)") (class "Default")
      (node (ref "U10") (pin "17") (pinfunction "DCO_17") (pintype "bidirectional+no_connect"))
    )
  )
)
